# Sheet_1_2023-10-06.net
KiCad netlist of a schematic drawn in Altium Designer
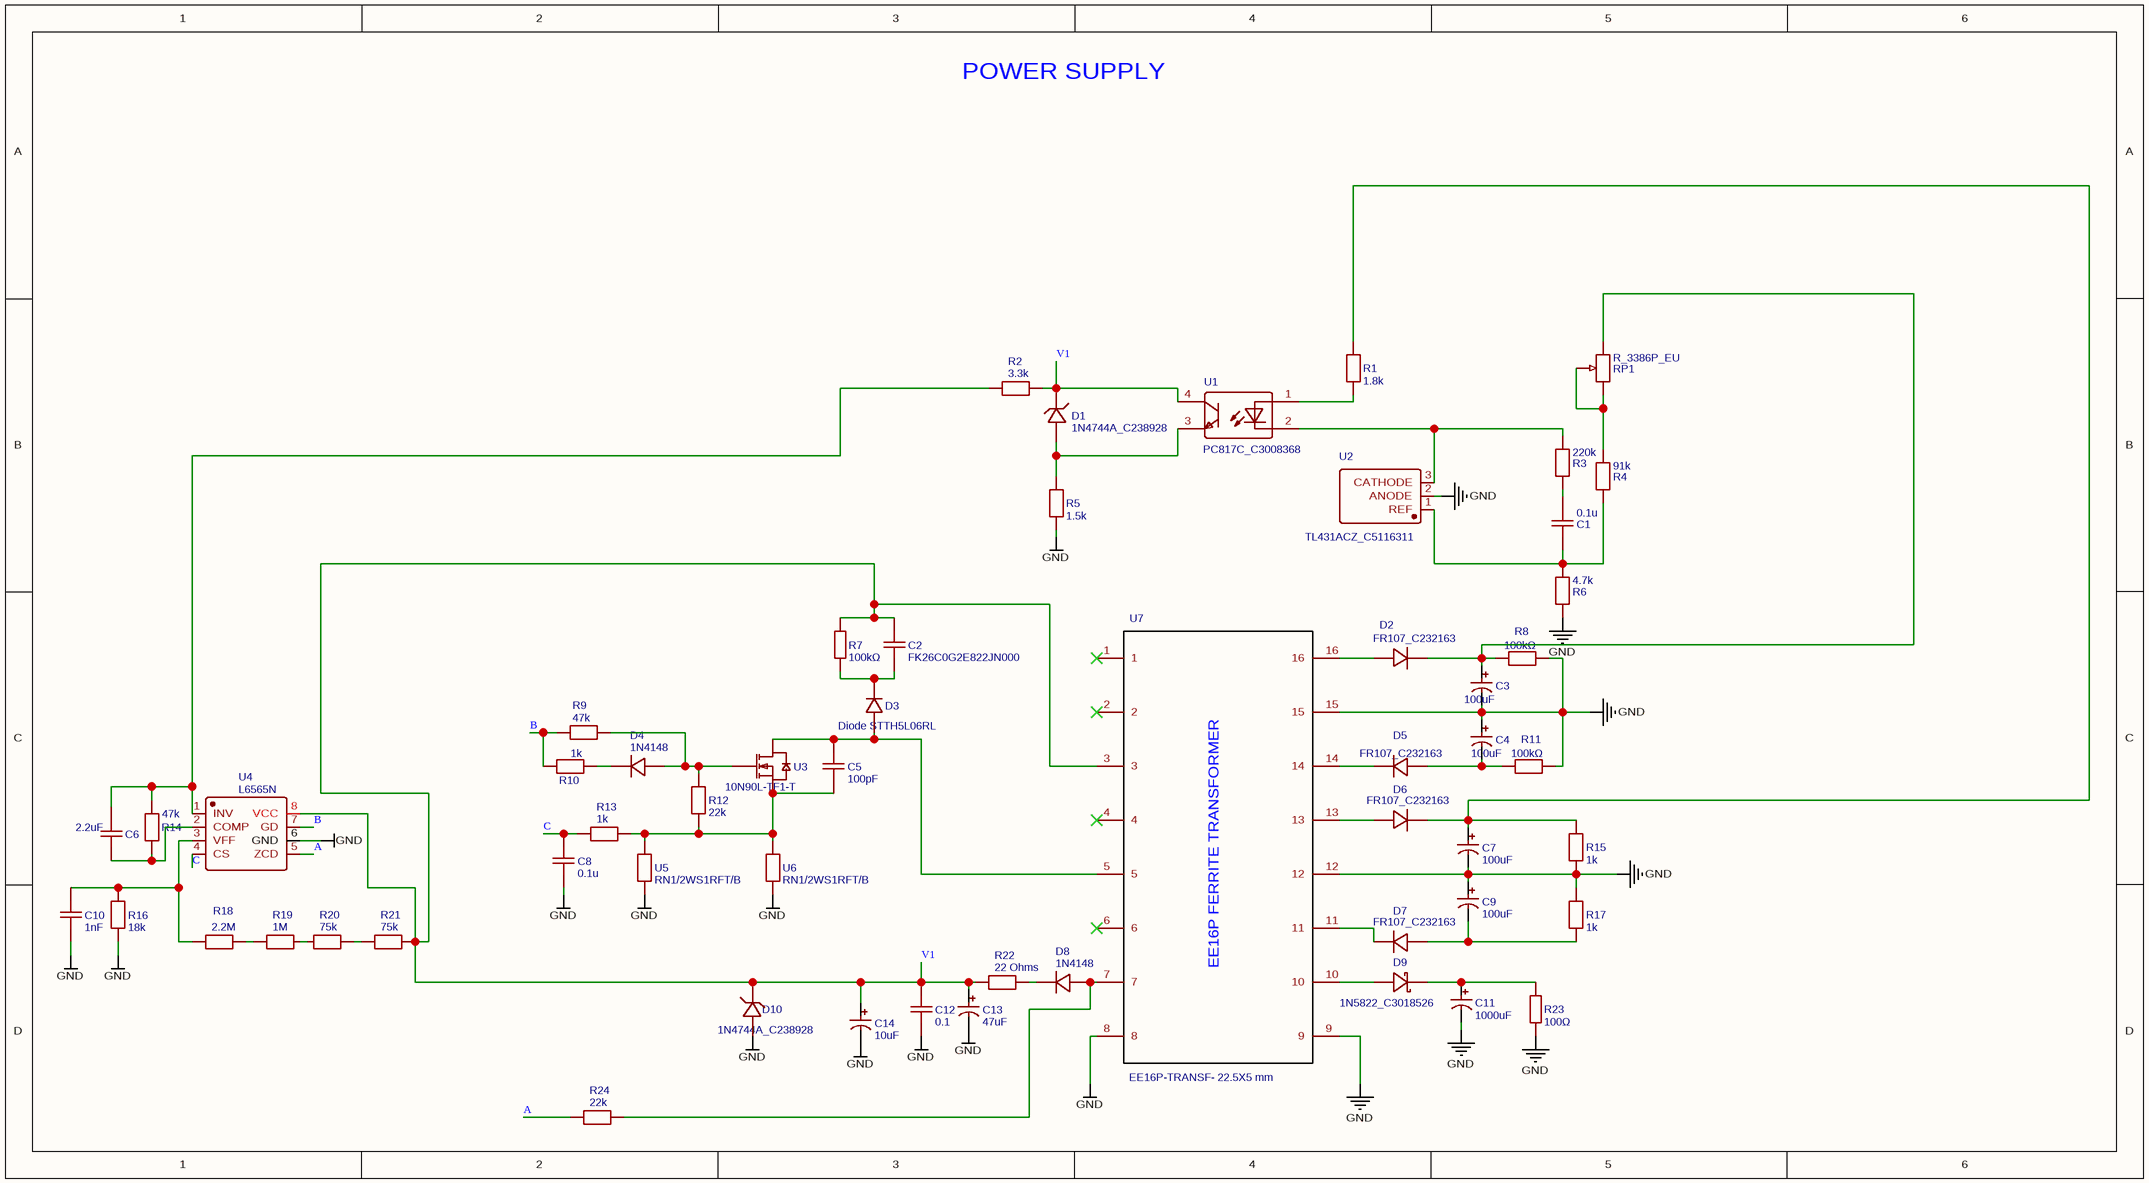
[diagram p0: Sheet_1_2023-10-06.schdoc]

(export (version "E")
  (design (tool "Eeschema 10.0.6"))
  (components
    (comp (ref "C1")
      (value "0.1u")
      (fields (field (name "CONTRIBUTOR") "LCEDA_Lib"))
      (libsource (lib "altium-import") (part "root_3_0.1u_"))
    )
    (comp (ref "C2")
      (value "FK26C0G2E822JN000")
      (fields (field (name "MANUFACTURER") "TDK") (field (name "CONTRIBUTOR") "lcsc"))
      (libsource (lib "altium-import") (part "root_1_FK26C0G2E822JN000_"))
    )
    (comp (ref "C3")
      (value "100uF")
      (fields (field (name "MANUFACTURER") "AISHI(艾华集团)") (field (name "MANUFACTURER PART") "ERS1KM101G16OT"))
      (libsource (lib "altium-import") (part "root_3_100uF_"))
    )
    (comp (ref "C4")
      (value "100uF")
      (fields (field (name "MANUFACTURER") "AISHI(艾华集团)") (field (name "MANUFACTURER PART") "ERS1KM101G16OT"))
      (libsource (lib "altium-import") (part "root_3_100uF_"))
    )
    (comp (ref "C5")
      (value "100pF")
      (fields
        (field (name "MANUFACTURER") "FH(风华)")
        (field (name "MANUFACTURER PART") "CT81-N6Y5P1B101KSEW")
        (field (name "CONTRIBUTOR") "LCSC")
      )
      (libsource (lib "altium-import") (part "root_1_100pF_"))
    )
    (comp (ref "C6")
      (value "2.2uF")
      (fields (field (name "CONTRIBUTOR") "LCEDA_Lib"))
      (libsource (lib "altium-import") (part "root_3_2.2uF_"))
    )
    (comp (ref "C7")
      (value "100uF")
      (fields (field (name "MANUFACTURER") "AISHI(艾华集团)") (field (name "MANUFACTURER PART") "ERS1VM101E12OT"))
      (libsource (lib "altium-import") (part "root_3_100uF_"))
    )
    (comp (ref "C8")
      (value "0.1u")
      (fields (field (name "CONTRIBUTOR") "LCEDA_Lib"))
      (libsource (lib "altium-import") (part "root_1_0.1u_"))
    )
    (comp (ref "C9")
      (value "100uF")
      (fields (field (name "MANUFACTURER") "AISHI(艾华集团)") (field (name "MANUFACTURER PART") "ERS1VM101E12OT"))
      (libsource (lib "altium-import") (part "root_3_100uF_"))
    )
    (comp (ref "C10")
      (value "1nF")
      (fields (field (name "CONTRIBUTOR") "LCEDA_Lib"))
      (libsource (lib "altium-import") (part "root_1_1nF_"))
    )
    (comp (ref "C11")
      (value "1000uF")
      (fields
        (field (name "MANUFACTURER") "CX(承兴)")
        (field (name "MANUFACTURER PART") "KM108M016G16RR0VH2FP0")
      )
      (libsource (lib "altium-import") (part "root_3_1000uF_"))
    )
    (comp (ref "C12")
      (value "0.1")
      (fields (field (name "CONTRIBUTOR") "LCEDA_Lib"))
      (libsource (lib "altium-import") (part "root_1_0.1_"))
    )
    (comp (ref "C13")
      (value "47uF")
      (fields
        (field (name "MANUFACTURER") "rubycon(红宝石)")
        (field (name "MANUFACTURER PART") "25YXF47MEFC5X11")
      )
      (libsource (lib "altium-import") (part "root_3_47uF_"))
    )
    (comp (ref "C14")
      (value "10uF")
      (fields
        (field (name "MANUFACTURER") "CX(承兴)")
        (field (name "MANUFACTURER PART") "KM106M025D11RR0VH2FP0")
      )
      (libsource (lib "altium-import") (part "root_3_10uF_"))
    )
    (comp (ref "D1")
      (value "1N4744A_C238928")
      (fields
        (field (name "MANUFACTURER") "onsemi(安森美)")
        (field (name "MANUFACTURER PART") "1N4744A")
        (field (name "CONTRIBUTOR") "LCSC")
      )
      (libsource (lib "") (part "root_3_1N4744A_C238928__1"))
    )
    (comp (ref "D2")
      (value "FR107_C232163")
      (fields
        (field (name "MANUFACTURER") "GD(固锝)")
        (field (name "MANUFACTURER PART") "FR107")
        (field (name "CONTRIBUTOR") "LCSC")
      )
      (libsource (lib "altium-import") (part "root_2_FR107_C232163_"))
    )
    (comp (ref "D3")
      (value "Diode STTH5L06RL")
      (fields
        (field (name "MANUFACTURER PART") "STMicroelectronics NV")
        (field (name "CONTRIBUTOR") "peteb2")
      )
      (libsource (lib "altium-import") (part "root_0_Diode STTH5L06RL_"))
    )
    (comp (ref "D4")
      (value "1N4148")
      (fields (field (name "MANUFACTURER") "ST(先科)"))
      (libsource (lib "altium-import") (part "root_2_1N4148_"))
    )
    (comp (ref "D5")
      (value "FR107_C232163")
      (fields
        (field (name "MANUFACTURER") "GD(固锝)")
        (field (name "MANUFACTURER PART") "FR107")
        (field (name "CONTRIBUTOR") "LCSC")
      )
      (libsource (lib "altium-import") (part "root_0_FR107_C232163_"))
    )
    (comp (ref "D6")
      (value "FR107_C232163")
      (fields
        (field (name "MANUFACTURER") "GD(固锝)")
        (field (name "MANUFACTURER PART") "FR107")
        (field (name "CONTRIBUTOR") "LCSC")
      )
      (libsource (lib "altium-import") (part "root_2_FR107_C232163_"))
    )
    (comp (ref "D7")
      (value "FR107_C232163")
      (fields
        (field (name "MANUFACTURER") "GD(固锝)")
        (field (name "MANUFACTURER PART") "FR107")
        (field (name "CONTRIBUTOR") "LCSC")
      )
      (libsource (lib "altium-import") (part "root_0_FR107_C232163_"))
    )
    (comp (ref "D8")
      (value "1N4148")
      (fields (field (name "MANUFACTURER") "ST(先科)"))
      (libsource (lib "altium-import") (part "root_2_1N4148_"))
    )
    (comp (ref "D9")
      (value "1N5822_C3018526")
      (fields
        (field (name "MANUFACTURER") "FUXINSEMI(富芯森美)")
        (field (name "MANUFACTURER PART") "1N5822")
        (field (name "CONTRIBUTOR") "lcsc")
      )
      (libsource (lib "altium-import") (part "root_2_1N5822_C3018526_"))
    )
    (comp (ref "D10")
      (value "1N4744A_C238928")
      (fields
        (field (name "MANUFACTURER") "onsemi(安森美)")
        (field (name "MANUFACTURER PART") "1N4744A")
        (field (name "CONTRIBUTOR") "LCSC")
      )
      (libsource (lib "altium-import") (part "root_3_1N4744A_C238928_"))
    )
    (comp (ref "R1")
      (value "1.8k")
      (fields (field (name "CONTRIBUTOR") "LCEDA_Lib"))
      (libsource (lib "altium-import") (part "root_3_1.8k_"))
    )
    (comp (ref "R2")
      (value "3.3k")
      (fields (field (name "CONTRIBUTOR") "LCEDA_Lib"))
      (libsource (lib "altium-import") (part "root_2_3.3k_"))
    )
    (comp (ref "R3")
      (value "220k")
      (fields (field (name "CONTRIBUTOR") "LCEDA_Lib"))
      (libsource (lib "altium-import") (part "root_3_220k_"))
    )
    (comp (ref "R4")
      (value "91k")
      (fields (field (name "CONTRIBUTOR") "LCEDA_Lib"))
      (libsource (lib "altium-import") (part "root_3_91k_"))
    )
    (comp (ref "R5")
      (value "1.5k")
      (fields (field (name "CONTRIBUTOR") "LCEDA_Lib"))
      (libsource (lib "altium-import") (part "root_3_1.5k_"))
    )
    (comp (ref "R6")
      (value "4.7k")
      (fields (field (name "CONTRIBUTOR") "LCEDA_Lib"))
      (libsource (lib "altium-import") (part "root_3_4.7k_"))
    )
    (comp (ref "R7")
      (value "100kΩ")
      (fields
        (field (name "MANUFACTURER") "CCO(千志电子)")
        (field (name "MANUFACTURER PART") "MF1W-100KΩ±1% T")
        (field (name "CONTRIBUTOR") "LCSC")
      )
      (libsource (lib "altium-import") (part "root_1_100kΩ_"))
    )
    (comp (ref "R8")
      (value "100kΩ")
      (fields
        (field (name "MANUFACTURER") "VISHAY(威世)")
        (field (name "MANUFACTURER PART") "VR37000001003FA100")
        (field (name "CONTRIBUTOR") "lcsc")
      )
      (libsource (lib "altium-import") (part "root_0_100kΩ_"))
    )
    (comp (ref "R9")
      (value "47k")
      (fields (field (name "CONTRIBUTOR") "LCEDA_Lib"))
      (libsource (lib "altium-import") (part "root_0_47k_"))
    )
    (comp (ref "R10")
      (value "1k")
      (fields (field (name "CONTRIBUTOR") "LCEDA_Lib"))
      (libsource (lib "altium-import") (part "root_0_1k_"))
    )
    (comp (ref "R11")
      (value "100kΩ")
      (fields
        (field (name "MANUFACTURER") "VISHAY(威世)")
        (field (name "MANUFACTURER PART") "VR37000001003FA100")
        (field (name "CONTRIBUTOR") "lcsc")
      )
      (libsource (lib "altium-import") (part "root_0_100kΩ_"))
    )
    (comp (ref "R12")
      (value "22k")
      (fields (field (name "CONTRIBUTOR") "LCEDA_Lib"))
      (libsource (lib "altium-import") (part "root_1_22k_"))
    )
    (comp (ref "R13")
      (value "1k")
      (fields (field (name "CONTRIBUTOR") "LCEDA_Lib"))
      (libsource (lib "altium-import") (part "root_0_1k_"))
    )
    (comp (ref "R14")
      (value "47k")
      (fields (field (name "CONTRIBUTOR") "LCEDA_Lib"))
      (libsource (lib "altium-import") (part "root_3_47k_"))
    )
    (comp (ref "R15")
      (value "1k")
      (fields (field (name "CONTRIBUTOR") "LCEDA_Lib"))
      (libsource (lib "altium-import") (part "root_1_1k_"))
    )
    (comp (ref "R16")
      (value "18k")
      (fields (field (name "CONTRIBUTOR") "LCEDA_Lib"))
      (libsource (lib "altium-import") (part "root_1_18k_"))
    )
    (comp (ref "R17")
      (value "1k")
      (fields (field (name "CONTRIBUTOR") "LCEDA_Lib"))
      (libsource (lib "altium-import") (part "root_1_1k_"))
    )
    (comp (ref "R18")
      (value "2.2M")
      (fields (field (name "CONTRIBUTOR") "LCEDA_Lib"))
      (libsource (lib "altium-import") (part "root_0_2.2M_"))
    )
    (comp (ref "R19")
      (value "1M")
      (fields (field (name "CONTRIBUTOR") "LCEDA_Lib"))
      (libsource (lib "altium-import") (part "root_0_1M_"))
    )
    (comp (ref "R20")
      (value "75k")
      (fields (field (name "CONTRIBUTOR") "LCEDA_Lib"))
      (libsource (lib "altium-import") (part "root_0_75k_"))
    )
    (comp (ref "R21")
      (value "75k")
      (fields (field (name "CONTRIBUTOR") "LCEDA_Lib"))
      (libsource (lib "altium-import") (part "root_0_75k_"))
    )
    (comp (ref "R22")
      (value "22 Ohms")
      (fields (field (name "CONTRIBUTOR") "LCEDA_Lib"))
      (libsource (lib "altium-import") (part "root_0_22 Ohms_"))
    )
    (comp (ref "R23")
      (value "100Ω")
      (fields
        (field (name "MANUFACTURER") "VO(翔胜)")
        (field (name "MANUFACTURER PART") "KNP1WS-100Ω±5%-XT52")
        (field (name "CONTRIBUTOR") "LCSC")
      )
      (libsource (lib "altium-import") (part "root_1_100Ω_"))
    )
    (comp (ref "R24")
      (value "22k")
      (fields (field (name "CONTRIBUTOR") "LCEDA_Lib"))
      (libsource (lib "altium-import") (part "root_0_22k_"))
    )
    (comp (ref "RP1")
      (value "R_3386P_EU")
      (fields (field (name "CONTRIBUTOR") "LCEDA_Lib"))
      (libsource (lib "altium-import") (part "root_1_R_3386P_EU_"))
    )
    (comp (ref "U1")
      (value "PC817C_C3008368")
      (fields
        (field (name "MANUFACTURER") "UMW(广东友台半导体)")
        (field (name "MANUFACTURER PART") "PC817C")
        (field (name "CONTRIBUTOR") "lcsc")
      )
      (libsource (lib "altium-import") (part "root_2_PC817C_C3008368_"))
    )
    (comp (ref "U2")
      (value "TL431ACZ_C5116311")
      (fields
        (field (name "MANUFACTURER") "HGSEMI(华冠)")
        (field (name "MANUFACTURER PART") "TL431ACZ")
        (field (name "CONTRIBUTOR") "lcsc")
      )
      (libsource (lib "altium-import") (part "root_2_TL431ACZ_C5116311_"))
    )
    (comp (ref "U3")
      (value "10N90L-TF1-T")
      (fields (field (name "MANUFACTURER") "UTC(友顺)") (field (name "CONTRIBUTOR") "lcsc"))
      (libsource (lib "altium-import") (part "root_0_10N90L-TF1-T_"))
    )
    (comp (ref "U4")
      (value "L6565N")
      (fields (field (name "MANUFACTURER") "ST(意法半导体)"))
      (libsource (lib "altium-import") (part "root_0_L6565N_"))
    )
    (comp (ref "U5")
      (value "RN1/2WS1RFT/B")
      (fields (field (name "MANUFACTURER") "Tyohm(幸亚电阻)") (field (name "CONTRIBUTOR") "lcsc"))
      (libsource (lib "altium-import") (part "root_1_RN1/2WS1RFT/B_"))
    )
    (comp (ref "U6")
      (value "RN1/2WS1RFT/B")
      (fields (field (name "MANUFACTURER") "Tyohm(幸亚电阻)") (field (name "CONTRIBUTOR") "lcsc"))
      (libsource (lib "altium-import") (part "root_1_RN1/2WS1RFT/B_"))
    )
    (comp (ref "U7")
      (value "EE16P-TRANSF- 22.5X5 mm")
      (fields (field (name "CONTRIBUTOR") "venkatakrishnanr"))
      (libsource (lib "altium-import") (part "root_0_EE16P-TRANSF- 22.5X5 mm_"))
    )
  )
  (nets
    (net (code "1") (name "/A") (class "Default")
      (node (ref "R24") (pin "1") (pinfunction "1_1") (pintype "passive"))
      (node (ref "U4") (pin "5") (pinfunction "ZCD_5") (pintype "passive"))
    )
    (net (code "2") (name "/B") (class "Default")
      (node (ref "R10") (pin "1") (pinfunction "1_1") (pintype "passive"))
      (node (ref "R9") (pin "1") (pinfunction "1_1") (pintype "passive"))
      (node (ref "U4") (pin "7") (pinfunction "GD_7") (pintype "passive"))
    )
    (net (code "3") (name "/C") (class "Default")
      (node (ref "C8") (pin "2") (pinfunction "2_2") (pintype "passive"))
      (node (ref "R13") (pin "1") (pinfunction "1_1") (pintype "passive"))
      (node (ref "U4") (pin "4") (pinfunction "CS_4") (pintype "passive"))
    )
    (net (code "4") (name "/V1") (class "Default")
      (node (ref "C12") (pin "2") (pinfunction "2_2") (pintype "passive"))
      (node (ref "C13") (pin "1") (pinfunction "1_1") (pintype "passive"))
      (node (ref "C14") (pin "1") (pinfunction "1_1") (pintype "passive"))
      (node (ref "C2") (pin "2") (pinfunction "2_2") (pintype "passive"))
      (node (ref "D1") (pin "1") (pinfunction "1_1") (pintype "passive"))
      (node (ref "D10") (pin "1") (pinfunction "1_1") (pintype "passive"))
      (node (ref "R2") (pin "1") (pinfunction "1_1") (pintype "passive"))
      (node (ref "R21") (pin "2") (pinfunction "2_2") (pintype "passive"))
      (node (ref "R22") (pin "1") (pinfunction "1_1") (pintype "passive"))
      (node (ref "R7") (pin "2") (pinfunction "2_2") (pintype "passive"))
      (node (ref "U1") (pin "4") (pinfunction "COL_4") (pintype "passive"))
      (node (ref "U4") (pin "8") (pinfunction "VCC_8") (pintype "passive"))
      (node (ref "U7") (pin "3") (pinfunction "3_3") (pintype "passive"))
    )
    (net (code "5") (name "GND") (class "Default")
      (node (ref "C10") (pin "1") (pinfunction "1_1") (pintype "passive"))
      (node (ref "C11") (pin "2") (pinfunction "2_2") (pintype "passive"))
      (node (ref "C12") (pin "1") (pinfunction "1_1") (pintype "passive"))
      (node (ref "C13") (pin "2") (pinfunction "2_2") (pintype "passive"))
      (node (ref "C14") (pin "2") (pinfunction "2_2") (pintype "passive"))
      (node (ref "C3") (pin "2") (pinfunction "2_2") (pintype "passive"))
      (node (ref "C4") (pin "1") (pinfunction "1_1") (pintype "passive"))
      (node (ref "C7") (pin "2") (pinfunction "2_2") (pintype "passive"))
      (node (ref "C8") (pin "1") (pinfunction "1_1") (pintype "passive"))
      (node (ref "C9") (pin "1") (pinfunction "1_1") (pintype "passive"))
      (node (ref "D10") (pin "2") (pinfunction "2_2") (pintype "passive"))
      (node (ref "R11") (pin "2") (pinfunction "2_2") (pintype "passive"))
      (node (ref "R15") (pin "1") (pinfunction "1_1") (pintype "passive"))
      (node (ref "R16") (pin "1") (pinfunction "1_1") (pintype "passive"))
      (node (ref "R17") (pin "2") (pinfunction "2_2") (pintype "passive"))
      (node (ref "R23") (pin "1") (pinfunction "1_1") (pintype "passive"))
      (node (ref "R5") (pin "2") (pinfunction "2_2") (pintype "passive"))
      (node (ref "R6") (pin "1") (pinfunction "1_1") (pintype "passive"))
      (node (ref "R8") (pin "2") (pinfunction "2_2") (pintype "passive"))
      (node (ref "U2") (pin "2") (pinfunction "ANODE_2") (pintype "passive"))
      (node (ref "U4") (pin "6") (pinfunction "GND_6") (pintype "passive"))
      (node (ref "U5") (pin "1") (pinfunction "1_1") (pintype "passive"))
      (node (ref "U6") (pin "1") (pinfunction "1_1") (pintype "passive"))
      (node (ref "U7") (pin "12") (pinfunction "12_12") (pintype "passive"))
      (node (ref "U7") (pin "15") (pinfunction "15_15") (pintype "passive"))
      (node (ref "U7") (pin "8") (pinfunction "8_8") (pintype "passive"))
      (node (ref "U7") (pin "9") (pinfunction "9_9") (pintype "passive"))
    )
    (net (code "6") (name "Net-(C1-Pad2)") (class "Default")
      (node (ref "C1") (pin "2") (pinfunction "2_2") (pintype "passive"))
      (node (ref "R3") (pin "1") (pinfunction "1_1") (pintype "passive"))
    )
    (net (code "7") (name "Net-(D2-A)") (class "Default")
      (node (ref "D2") (pin "2") (pinfunction "A_2") (pintype "passive"))
      (node (ref "U7") (pin "16") (pinfunction "16_16") (pintype "passive"))
    )
    (net (code "8") (name "Net-(D2-C)") (class "Default")
      (node (ref "C3") (pin "1") (pinfunction "1_1") (pintype "passive"))
      (node (ref "D2") (pin "1") (pinfunction "C_1") (pintype "passive"))
      (node (ref "R8") (pin "1") (pinfunction "1_1") (pintype "passive"))
      (node (ref "RP1") (pin "1") (pinfunction "1_1") (pintype "passive"))
    )
    (net (code "9") (name "Net-(D3-A)") (class "Default")
      (node (ref "C5") (pin "2") (pinfunction "2_2") (pintype "passive"))
      (node (ref "D3") (pin "1") (pinfunction "A_1") (pintype "passive"))
      (node (ref "U3") (pin "2") (pinfunction "D_2") (pintype "passive"))
      (node (ref "U7") (pin "5") (pinfunction "5_5") (pintype "passive"))
    )
    (net (code "10") (name "Net-(D3-K)") (class "Default")
      (node (ref "C2") (pin "1") (pinfunction "1_1") (pintype "passive"))
      (node (ref "D3") (pin "2") (pinfunction "K_2") (pintype "passive"))
      (node (ref "R7") (pin "1") (pinfunction "1_1") (pintype "passive"))
    )
    (net (code "11") (name "Net-(D4-A)") (class "Default")
      (node (ref "D4") (pin "1") (pinfunction "A_1") (pintype "passive"))
      (node (ref "R12") (pin "2") (pinfunction "2_2") (pintype "passive"))
      (node (ref "R9") (pin "2") (pinfunction "2_2") (pintype "passive"))
      (node (ref "U3") (pin "1") (pinfunction "G_1") (pintype "passive"))
    )
    (net (code "12") (name "Net-(D4-C)") (class "Default")
      (node (ref "D4") (pin "2") (pinfunction "C_2") (pintype "passive"))
      (node (ref "R10") (pin "2") (pinfunction "2_2") (pintype "passive"))
    )
    (net (code "13") (name "Net-(D5-A)") (class "Default")
      (node (ref "C4") (pin "2") (pinfunction "2_2") (pintype "passive"))
      (node (ref "D5") (pin "2") (pinfunction "A_2") (pintype "passive"))
      (node (ref "R11") (pin "1") (pinfunction "1_1") (pintype "passive"))
    )
    (net (code "14") (name "Net-(D5-C)") (class "Default")
      (node (ref "D5") (pin "1") (pinfunction "C_1") (pintype "passive"))
      (node (ref "U7") (pin "14") (pinfunction "14_14") (pintype "passive"))
    )
    (net (code "15") (name "Net-(D6-A)") (class "Default")
      (node (ref "D6") (pin "2") (pinfunction "A_2") (pintype "passive"))
      (node (ref "U7") (pin "13") (pinfunction "13_13") (pintype "passive"))
    )
    (net (code "16") (name "Net-(D6-C)") (class "Default")
      (node (ref "C7") (pin "1") (pinfunction "1_1") (pintype "passive"))
      (node (ref "D6") (pin "1") (pinfunction "C_1") (pintype "passive"))
      (node (ref "R1") (pin "1") (pinfunction "1_1") (pintype "passive"))
      (node (ref "R15") (pin "2") (pinfunction "2_2") (pintype "passive"))
    )
    (net (code "17") (name "Net-(D7-A)") (class "Default")
      (node (ref "C9") (pin "2") (pinfunction "2_2") (pintype "passive"))
      (node (ref "D7") (pin "2") (pinfunction "A_2") (pintype "passive"))
      (node (ref "R17") (pin "1") (pinfunction "1_1") (pintype "passive"))
    )
    (net (code "18") (name "Net-(D7-C)") (class "Default")
      (node (ref "D7") (pin "1") (pinfunction "C_1") (pintype "passive"))
      (node (ref "U7") (pin "11") (pinfunction "11_11") (pintype "passive"))
    )
    (net (code "19") (name "Net-(D8-A)") (class "Default")
      (node (ref "D8") (pin "1") (pinfunction "A_1") (pintype "passive"))
      (node (ref "R24") (pin "2") (pinfunction "2_2") (pintype "passive"))
      (node (ref "U7") (pin "7") (pinfunction "7_7") (pintype "passive"))
    )
    (net (code "20") (name "Net-(D8-C)") (class "Default")
      (node (ref "D8") (pin "2") (pinfunction "C_2") (pintype "passive"))
      (node (ref "R22") (pin "2") (pinfunction "2_2") (pintype "passive"))
    )
    (net (code "21") (name "Net-(D9-A)") (class "Default")
      (node (ref "D9") (pin "1") (pinfunction "A_1") (pintype "passive"))
      (node (ref "U7") (pin "10") (pinfunction "10_10") (pintype "passive"))
    )
    (net (code "22") (name "Net-(D9-K)") (class "Default")
      (node (ref "C11") (pin "1") (pinfunction "1_1") (pintype "passive"))
      (node (ref "D9") (pin "2") (pinfunction "K_2") (pintype "passive"))
      (node (ref "R23") (pin "2") (pinfunction "2_2") (pintype "passive"))
    )
    (net (code "23") (name "Net-(R4-Pad2)") (class "Default")
      (node (ref "R4") (pin "2") (pinfunction "2_2") (pintype "passive"))
      (node (ref "RP1") (pin "2") (pinfunction "2_2") (pintype "passive"))
      (node (ref "RP1") (pin "3") (pinfunction "3_3") (pintype "passive"))
    )
    (net (code "24") (name "Net-(R18-Pad2)") (class "Default")
      (node (ref "R18") (pin "2") (pinfunction "2_2") (pintype "passive"))
      (node (ref "R19") (pin "1") (pinfunction "1_1") (pintype "passive"))
    )
    (net (code "25") (name "Net-(R19-Pad2)") (class "Default")
      (node (ref "R19") (pin "2") (pinfunction "2_2") (pintype "passive"))
      (node (ref "R20") (pin "1") (pinfunction "1_1") (pintype "passive"))
    )
    (net (code "26") (name "Net-(R20-Pad2)") (class "Default")
      (node (ref "R20") (pin "2") (pinfunction "2_2") (pintype "passive"))
      (node (ref "R21") (pin "1") (pinfunction "1_1") (pintype "passive"))
    )
    (net (code "27") (name "Net-(U1-AN)") (class "Default")
      (node (ref "R1") (pin "2") (pinfunction "2_2") (pintype "passive"))
      (node (ref "U1") (pin "1") (pinfunction "AN_1") (pintype "passive"))
    )
    (net (code "28") (name "Net-(U1-CAT)") (class "Default")
      (node (ref "R3") (pin "2") (pinfunction "2_2") (pintype "passive"))
      (node (ref "U1") (pin "2") (pinfunction "CAT_2") (pintype "passive"))
      (node (ref "U2") (pin "3") (pinfunction "CATHODE_3") (pintype "passive"))
    )
    (net (code "29") (name "Net-(U1-EM)") (class "Default")
      (node (ref "D1") (pin "2") (pinfunction "2_2") (pintype "passive"))
      (node (ref "R5") (pin "1") (pinfunction "1_1") (pintype "passive"))
      (node (ref "U1") (pin "3") (pinfunction "EM_3") (pintype "passive"))
    )
    (net (code "30") (name "Net-(U2-REF)") (class "Default")
      (node (ref "C1") (pin "1") (pinfunction "1_1") (pintype "passive"))
      (node (ref "R4") (pin "1") (pinfunction "1_1") (pintype "passive"))
      (node (ref "R6") (pin "2") (pinfunction "2_2") (pintype "passive"))
      (node (ref "U2") (pin "1") (pinfunction "REF_1") (pintype "passive"))
    )
    (net (code "31") (name "Net-(U3-S)") (class "Default")
      (node (ref "C5") (pin "1") (pinfunction "1_1") (pintype "passive"))
      (node (ref "R12") (pin "1") (pinfunction "1_1") (pintype "passive"))
      (node (ref "R13") (pin "2") (pinfunction "2_2") (pintype "passive"))
      (node (ref "U3") (pin "3") (pinfunction "S_3") (pintype "passive"))
      (node (ref "U5") (pin "2") (pinfunction "2_2") (pintype "passive"))
      (node (ref "U6") (pin "2") (pinfunction "2_2") (pintype "passive"))
    )
    (net (code "32") (name "Net-(U4-COMP)") (class "Default")
      (node (ref "C6") (pin "2") (pinfunction "2_2") (pintype "passive"))
      (node (ref "R14") (pin "2") (pinfunction "2_2") (pintype "passive"))
      (node (ref "U4") (pin "2") (pinfunction "COMP_2") (pintype "passive"))
    )
    (net (code "33") (name "Net-(U4-INV)") (class "Default")
      (node (ref "C6") (pin "1") (pinfunction "1_1") (pintype "passive"))
      (node (ref "R14") (pin "1") (pinfunction "1_1") (pintype "passive"))
      (node (ref "R2") (pin "2") (pinfunction "2_2") (pintype "passive"))
      (node (ref "U4") (pin "1") (pinfunction "INV_1") (pintype "passive"))
    )
    (net (code "34") (name "Net-(U4-VFF)") (class "Default")
      (node (ref "C10") (pin "2") (pinfunction "2_2") (pintype "passive"))
      (node (ref "R16") (pin "2") (pinfunction "2_2") (pintype "passive"))
      (node (ref "R18") (pin "1") (pinfunction "1_1") (pintype "passive"))
      (node (ref "U4") (pin "3") (pinfunction "VFF_3") (pintype "passive"))
    )
    (net (code "35") (name "unconnected-(U7-Pad1)") (class "Default")
      (node (ref "U7") (pin "1") (pinfunction "1_1") (pintype "passive+no_connect"))
    )
    (net (code "36") (name "unconnected-(U7-Pad2)") (class "Default")
      (node (ref "U7") (pin "2") (pinfunction "2_2") (pintype "passive+no_connect"))
    )
    (net (code "37") (name "unconnected-(U7-Pad4)") (class "Default")
      (node (ref "U7") (pin "4") (pinfunction "4_4") (pintype "passive+no_connect"))
    )
    (net (code "38") (name "unconnected-(U7-Pad6)") (class "Default")
      (node (ref "U7") (pin "6") (pinfunction "6_6") (pintype "passive+no_connect"))
    )
  )
)
